# DB10005_USBSerial.net
KiCad netlist of a schematic drawn in Altium Designer
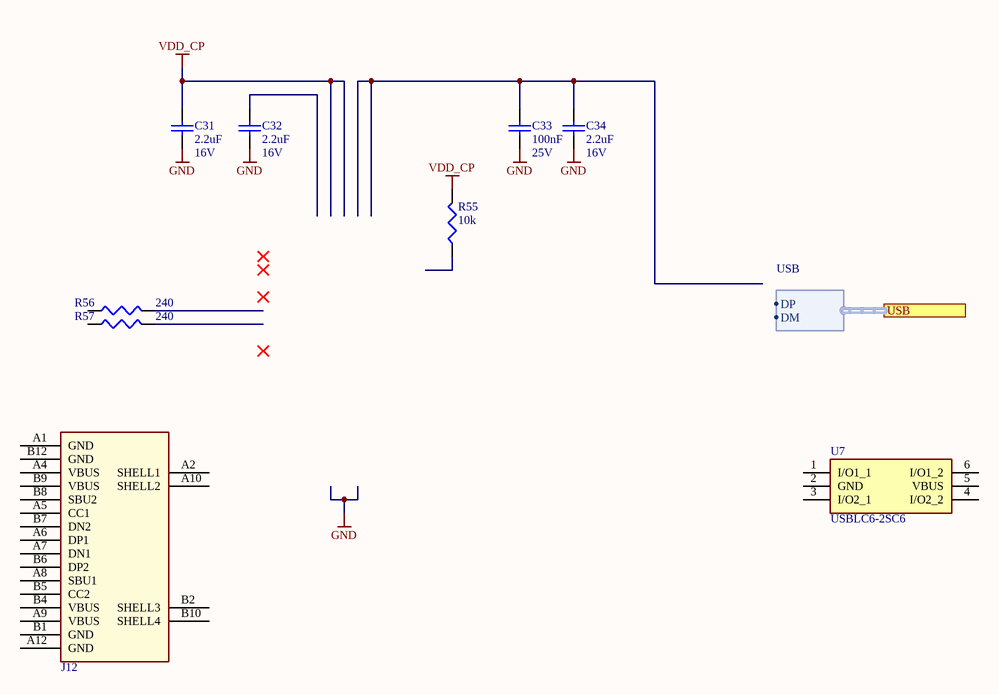
[diagram p0: DB10005_USBSerial.SchDoc]

(export (version "E")
  (design (tool "Eeschema 10.0.6"))
  (components
    (comp (ref "C31")
      (value "2.2uF")
      (footprint "C0603")
      (description "Capacitor, 2.2uF, 16V, X5R")
      (fields (field (name "VOLTAGE RATING") "16V"))
      (libsource (lib "AR_Capacitors_Ceramic") (part "2.2uF/0603/CER/16V"))
    )
    (comp (ref "C32")
      (value "2.2uF")
      (footprint "C0603")
      (description "Capacitor, 2.2uF, 16V, X5R")
      (fields (field (name "VOLTAGE RATING") "16V"))
      (libsource (lib "AR_Capacitors_Ceramic") (part "2.2uF/0603/CER/16V"))
    )
    (comp (ref "C33")
      (value "100nF")
      (footprint "C0402")
      (description "Capacitor, 100nF, 25V, X7R")
      (fields (field (name "VOLTAGE RATING") "25V"))
      (libsource (lib "AR_Capacitors_Ceramic") (part "100nF/0402/CER/25V"))
    )
    (comp (ref "C34")
      (value "2.2uF")
      (footprint "C0603")
      (description "Capacitor, 2.2uF, 16V, X5R")
      (fields (field (name "VOLTAGE RATING") "16V"))
      (libsource (lib "AR_Capacitors_Ceramic") (part "2.2uF/0603/CER/16V"))
    )
    (comp (ref "J12")
      (value "TYPE-C 16PLC-H10.0")
      (footprint "TYPE-C-TH_16PLC-H10.0")
      (description "连接器类型:Type-C;标准:USB 3.1;公母:母;安装方式:直插;触点数量:16P;端口数量:1;额定电流 - 电源:5A;触头材质:-;触头镀层:-;工作温度范围:-40℃~+85℃;")
      (fields (field (name "MANUFACTURER") "SHOU HAN(首韩)"))
      (libsource (lib "DB10005_DieBieMS") (part "TYPE-C 16PLC-H10.0"))
    )
    (comp (ref "R55")
      (value "10k")
      (footprint "0402")
      (description "Resistor, 10k, 0.1%, 0.0625W, 50V, 100PPM, 0402")
      (libsource (lib "AR_Resistors_SMD") (part "10k/0402/0063W/50V"))
    )
    (comp (ref "R56")
      (value "240")
      (footprint "0402")
      (description "Resistor, 240, 0.1%, 0.0625W, 50V, 100PPM, 0402")
      (libsource (lib "AR_Resistors_SMD") (part "240/0402/0063W/50V"))
    )
    (comp (ref "R57")
      (value "240")
      (footprint "0402")
      (description "Resistor, 240, 0.1%, 0.0625W, 50V, 100PPM, 0402")
      (libsource (lib "AR_Resistors_SMD") (part "240/0402/0063W/50V"))
    )
    (comp (ref "U7")
      (value "USBLC6-2SC6")
      (footprint "SOT95P280X145-6N")
      (description "Integrated Circuit")
      (fields (field (name "MOUSER PART NUMBER") "511-USBLC6-2SC6"))
      (libsource (lib "DB10005_DieBieMS") (part "USBLC6-2SC6"))
    )
  )
  (nets
    (net (code "3") (name "GND") (class "Default")
      (node (ref "C31") (pin "1") (pinfunction "1_1") (pintype "passive"))
      (node (ref "C32") (pin "1") (pinfunction "1_1") (pintype "passive"))
      (node (ref "C33") (pin "1") (pinfunction "1_1") (pintype "passive"))
      (node (ref "C34") (pin "1") (pinfunction "1_1") (pintype "passive"))
    )
    (net (code "4") (name "Net-(C33-Pad2)") (class "Default")
      (node (ref "C33") (pin "2") (pinfunction "2_2") (pintype "passive"))
      (node (ref "C34") (pin "2") (pinfunction "2_2") (pintype "passive"))
    )
    (net (code "5") (name "VDD_CP") (class "Default")
      (node (ref "C31") (pin "2") (pinfunction "2_2") (pintype "passive"))
      (node (ref "R55") (pin "2") (pinfunction "2_2") (pintype "passive"))
    )
    (net (code "6") (name "unconnected-(C32-Pad2)") (class "Default")
      (node (ref "C32") (pin "2") (pinfunction "2_2") (pintype "passive"))
    )
    (net (code "7") (name "unconnected-(J12-CC1-PadA5)") (class "Default")
      (node (ref "J12") (pin "A5") (pinfunction "CC1_A5") (pintype "passive"))
    )
    (net (code "8") (name "unconnected-(J12-CC2-PadB5)") (class "Default")
      (node (ref "J12") (pin "B5") (pinfunction "CC2_B5") (pintype "passive"))
    )
    (net (code "9") (name "unconnected-(J12-DN1-PadA7)") (class "Default")
      (node (ref "J12") (pin "A7") (pinfunction "DN1_A7") (pintype "passive"))
    )
    (net (code "10") (name "unconnected-(J12-DN2-PadB7)") (class "Default")
      (node (ref "J12") (pin "B7") (pinfunction "DN2_B7") (pintype "passive"))
    )
    (net (code "11") (name "unconnected-(J12-DP1-PadA6)") (class "Default")
      (node (ref "J12") (pin "A6") (pinfunction "DP1_A6") (pintype "passive"))
    )
    (net (code "12") (name "unconnected-(J12-DP2-PadB6)") (class "Default")
      (node (ref "J12") (pin "B6") (pinfunction "DP2_B6") (pintype "passive"))
    )
    (net (code "13") (name "unconnected-(J12-GND-PadA1)") (class "Default")
      (node (ref "J12") (pin "A1") (pinfunction "GND_A1") (pintype "power_in"))
    )
    (net (code "14") (name "unconnected-(J12-GND-PadA12)") (class "Default")
      (node (ref "J12") (pin "A12") (pinfunction "GND_A12") (pintype "power_in"))
    )
    (net (code "15") (name "unconnected-(J12-GND-PadB1)") (class "Default")
      (node (ref "J12") (pin "B1") (pinfunction "GND_B1") (pintype "power_in"))
    )
    (net (code "16") (name "unconnected-(J12-GND-PadB12)") (class "Default")
      (node (ref "J12") (pin "B12") (pinfunction "GND_B12") (pintype "power_in"))
    )
    (net (code "17") (name "unconnected-(J12-SBU1-PadA8)") (class "Default")
      (node (ref "J12") (pin "A8") (pinfunction "SBU1_A8") (pintype "passive"))
    )
    (net (code "18") (name "unconnected-(J12-SBU2-PadB8)") (class "Default")
      (node (ref "J12") (pin "B8") (pinfunction "SBU2_B8") (pintype "passive"))
    )
    (net (code "19") (name "unconnected-(J12-SHELL1-PadA2)") (class "Default")
      (node (ref "J12") (pin "A2") (pinfunction "SHELL1_A2") (pintype "power_in"))
    )
    (net (code "20") (name "unconnected-(J12-SHELL2-PadA10)") (class "Default")
      (node (ref "J12") (pin "A10") (pinfunction "SHELL2_A10") (pintype "power_in"))
    )
    (net (code "21") (name "unconnected-(J12-SHELL3-PadB2)") (class "Default")
      (node (ref "J12") (pin "B2") (pinfunction "SHELL3_B2") (pintype "power_in"))
    )
    (net (code "22") (name "unconnected-(J12-SHELL4-PadB10)") (class "Default")
      (node (ref "J12") (pin "B10") (pinfunction "SHELL4_B10") (pintype "power_in"))
    )
    (net (code "23") (name "unconnected-(J12-VBUS-PadA4)") (class "Default")
      (node (ref "J12") (pin "A4") (pinfunction "VBUS_A4") (pintype "power_in"))
    )
    (net (code "24") (name "unconnected-(J12-VBUS-PadA9)") (class "Default")
      (node (ref "J12") (pin "A9") (pinfunction "VBUS_A9") (pintype "power_in"))
    )
    (net (code "25") (name "unconnected-(J12-VBUS-PadB4)") (class "Default")
      (node (ref "J12") (pin "B4") (pinfunction "VBUS_B4") (pintype "power_in"))
    )
    (net (code "26") (name "unconnected-(J12-VBUS-PadB9)") (class "Default")
      (node (ref "J12") (pin "B9") (pinfunction "VBUS_B9") (pintype "power_in"))
    )
    (net (code "27") (name "unconnected-(R55-Pad1)") (class "Default")
      (node (ref "R55") (pin "1") (pinfunction "1_1") (pintype "passive"))
    )
    (net (code "28") (name "unconnected-(R56-Pad1)") (class "Default")
      (node (ref "R56") (pin "1") (pinfunction "1_1") (pintype "passive"))
    )
    (net (code "29") (name "unconnected-(R56-Pad2)") (class "Default")
      (node (ref "R56") (pin "2") (pinfunction "2_2") (pintype "passive"))
    )
    (net (code "30") (name "unconnected-(R57-Pad1)") (class "Default")
      (node (ref "R57") (pin "1") (pinfunction "1_1") (pintype "passive"))
    )
    (net (code "31") (name "unconnected-(R57-Pad2)") (class "Default")
      (node (ref "R57") (pin "2") (pinfunction "2_2") (pintype "passive"))
    )
    (net (code "32") (name "unconnected-(U7-GND-Pad2)") (class "Default")
      (node (ref "U7") (pin "2") (pinfunction "GND_2") (pintype "passive"))
    )
    (net (code "33") (name "unconnected-(U7-I{slash}O1_1-Pad1)") (class "Default")
      (node (ref "U7") (pin "1") (pinfunction "I/O1_1_1") (pintype "passive"))
    )
    (net (code "34") (name "unconnected-(U7-I{slash}O1_2-Pad6)") (class "Default")
      (node (ref "U7") (pin "6") (pinfunction "I/O1_2_6") (pintype "passive"))
    )
    (net (code "35") (name "unconnected-(U7-I{slash}O2_1-Pad3)") (class "Default")
      (node (ref "U7") (pin "3") (pinfunction "I/O2_1_3") (pintype "passive"))
    )
    (net (code "36") (name "unconnected-(U7-I{slash}O2_2-Pad4)") (class "Default")
      (node (ref "U7") (pin "4") (pinfunction "I/O2_2_4") (pintype "passive"))
    )
    (net (code "37") (name "unconnected-(U7-VBUS-Pad5)") (class "Default")
      (node (ref "U7") (pin "5") (pinfunction "VBUS_5") (pintype "passive"))
    )
  )
)
